# Placa_Motor_Esquematico.net
KiCad netlist of a schematic drawn in Altium Designer
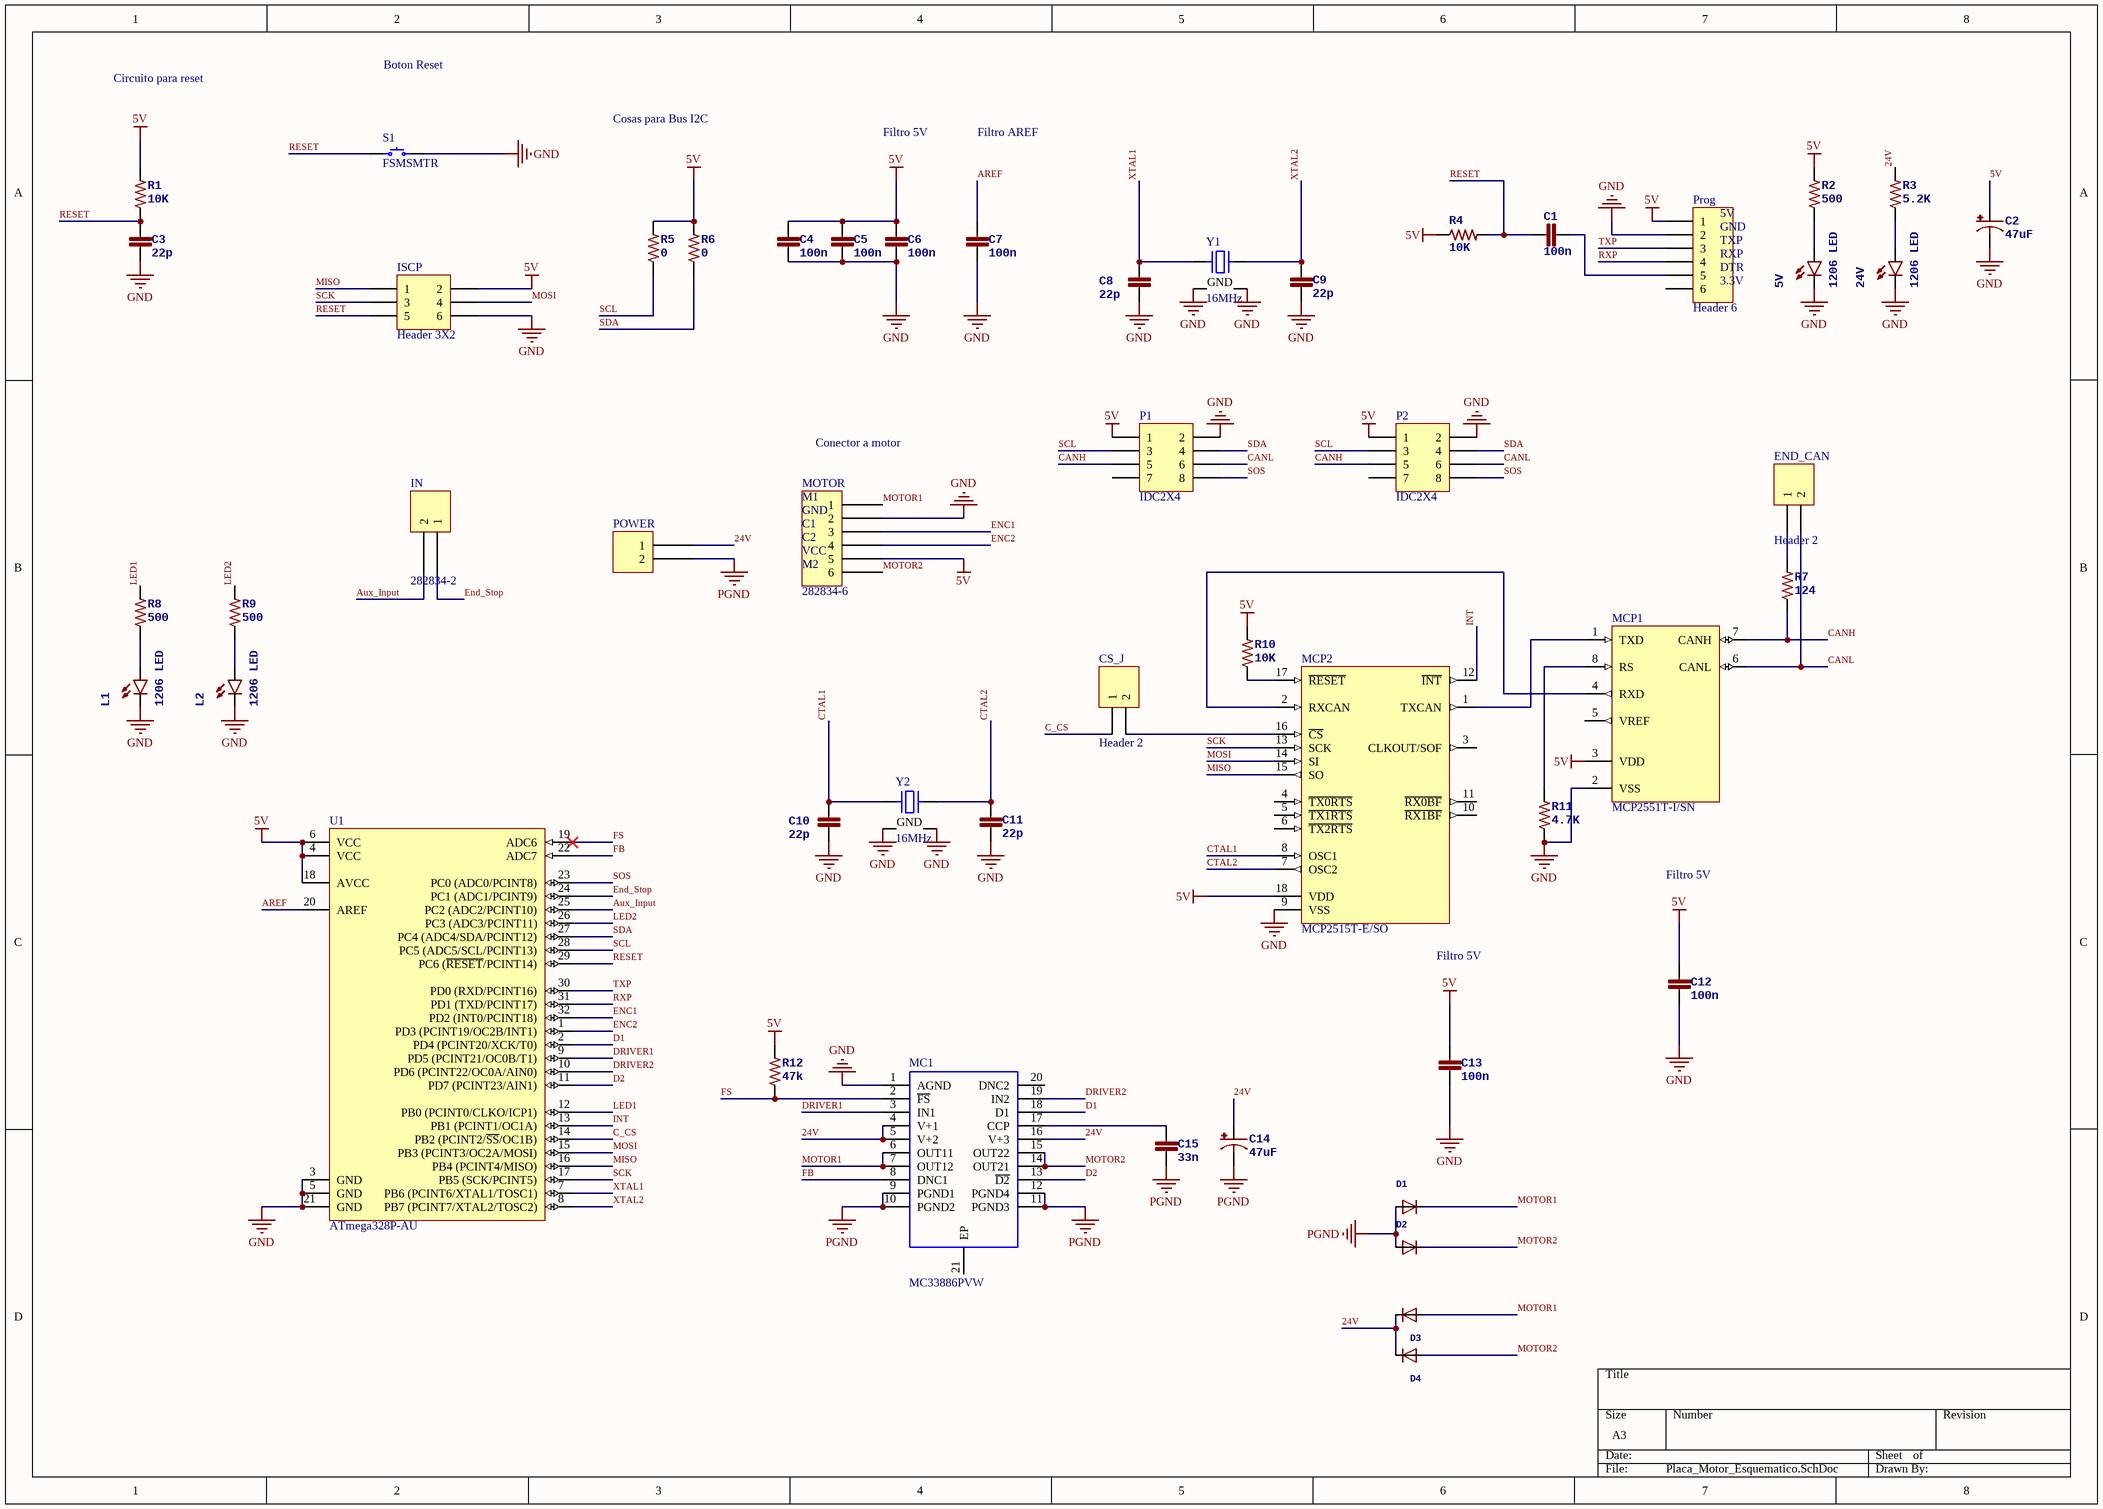
[diagram p0: Placa_Motor_Esquematico.SchDoc]

(export (version "E")
  (design (tool "Eeschema 10.0.6"))
  (components
    (comp (ref "5V")
      (value "1206 LED")
      (footprint "LED-1206")
      (libsource (lib "SparkFun-LED") (part "LED1206"))
    )
    (comp (ref "24V")
      (value "1206 LED")
      (footprint "LED-1206")
      (libsource (lib "SparkFun-LED") (part "LED1206"))
    )
    (comp (ref "C1") (value "100n") (footprint "0805") (libsource (lib "") (part "CAP0805_1")))
    (comp (ref "C2")
      (value "47uF")
      (footprint "PANASONIC_D")
      (libsource (lib "SparkFun-Capacitors") (part "47UF-50V-20%(ELECT)"))
    )
    (comp (ref "C3") (value "22p") (footprint "0805") (libsource (lib "SparkFun-Passives") (part "CAP0805")))
    (comp (ref "C4") (value "100n") (footprint "0805") (libsource (lib "SparkFun-Passives") (part "CAP0805")))
    (comp (ref "C5") (value "100n") (footprint "0805") (libsource (lib "SparkFun-Passives") (part "CAP0805")))
    (comp (ref "C6") (value "100n") (footprint "0805") (libsource (lib "SparkFun-Passives") (part "CAP0805")))
    (comp (ref "C7") (value "100n") (footprint "0805") (libsource (lib "SparkFun-Passives") (part "CAP0805")))
    (comp (ref "C8") (value "22p") (footprint "0805") (libsource (lib "SparkFun-Passives") (part "CAP0805")))
    (comp (ref "C9") (value "22p") (footprint "0805") (libsource (lib "SparkFun-Passives") (part "CAP0805")))
    (comp (ref "C10") (value "22p") (footprint "0805") (libsource (lib "SparkFun-Passives") (part "CAP0805")))
    (comp (ref "C11") (value "22p") (footprint "0805") (libsource (lib "SparkFun-Passives") (part "CAP0805")))
    (comp (ref "C12")
      (value "100n")
      (footprint "0805")
      (libsource (lib "SparkFun-Passives") (part "CAP0805"))
    )
    (comp (ref "C13")
      (value "100n")
      (footprint "0805")
      (libsource (lib "SparkFun-Passives") (part "CAP0805"))
    )
    (comp (ref "C14")
      (value "47uF")
      (footprint "PANASONIC_D")
      (libsource (lib "SparkFun-Capacitors") (part "47UF-50V-20%(ELECT)"))
    )
    (comp (ref "C15") (value "33n") (footprint "0805") (libsource (lib "SparkFun-Passives") (part "CAP0805")))
    (comp (ref "CS_J")
      (value "Header 2")
      (footprint "HDR1X2")
      (description "Header, 2-Pin")
      (fields (field (name "PUBLISHER") "Altium Limited"))
      (libsource (lib "Miscellaneous Connectors") (part "Header 2"))
    )
    (comp (ref "D1")
      (value "SBR3U40P1-7")
      (footprint "POWERDI-123")
      (libsource (lib "diodes-inc") (part "DFLS1100-7"))
    )
    (comp (ref "D2")
      (value "SBR3U40P1-7")
      (footprint "POWERDI-123")
      (libsource (lib "diodes-inc") (part "DFLS1100-7"))
    )
    (comp (ref "D3")
      (value "SBR3U40P1-7")
      (footprint "POWERDI-123")
      (libsource (lib "diodes-inc") (part "DFLS1100-7"))
    )
    (comp (ref "D4")
      (value "SBR3U40P1-7")
      (footprint "POWERDI-123")
      (libsource (lib "diodes-inc") (part "DFLS1100-7"))
    )
    (comp (ref "END_CAN")
      (value "Header 2")
      (footprint "HDR1X2")
      (description "Header, 2-Pin")
      (fields (field (name "PUBLISHER") "Altium Limited"))
      (libsource (lib "Miscellaneous Connectors") (part "Header 2"))
    )
    (comp (ref "IN")
      (value "282834-2")
      (footprint "TE 282834-2")
      (description "TERM BLOCK 2POS SIDE ENT 2.54MM")
      (fields (field (name "MANUFACTURER") "TE Connectivity AMP Connectors") (field (name "VOLTAGE") "150V"))
      (libsource (lib "Connector - Terminal Block") (part "2 Pin"))
    )
    (comp (ref "ISCP")
      (value "Header 3X2")
      (footprint "HDR2X3")
      (description "Header, 3-Pin, Dual row")
      (fields (field (name "PUBLISHER") "Altium Limited"))
      (libsource (lib "Miscellaneous Connectors") (part "Header 3X2"))
    )
    (comp (ref "L1")
      (value "1206 LED")
      (footprint "LED-1206")
      (libsource (lib "SparkFun-LED") (part "LED1206"))
    )
    (comp (ref "L2")
      (value "1206 LED")
      (footprint "LED-1206")
      (libsource (lib "SparkFun-LED") (part "LED1206"))
    )
    (comp (ref "MC1")
      (value "MC33886PVW")
      (footprint "SOIC127P1420X340-21N")
      (description "Motor / Motion / Ignition Controllers & Drivers 5.0 A H-BRIDGE")
      (libsource (lib "MC33886PVW") (part "MC33886PVW"))
    )
    (comp (ref "MCP1")
      (value "MCP2551T-I/SN")
      (footprint "SOIC-SN8_N")
      (description "High-Speed CAN Transceiver, 8-Pin SOIC, Industrial Temperature, Tape and Reel")
      (fields (field (name "PUBLISHER") "Altium Limited"))
      (libsource (lib "Microchip Interface") (part "MCP2551T-I/SN"))
    )
    (comp (ref "MCP2")
      (value "MCP2515T-E/SO")
      (footprint "SOIC-SO18_N")
      (description "Stand-Alone CAN Controller With SPI Interface, 18-Pin SOIC, Extended Temperature, Tape and Reel")
      (fields (field (name "PUBLISHER") "Altium Limited"))
      (libsource (lib "Microchip Interface") (part "MCP2515T-E/SO"))
    )
    (comp (ref "MOTOR")
      (value "282834-6")
      (footprint "TE 282834-6")
      (description "TERM BLOCK 6POS SIDE ENT 2.54MM")
      (fields (field (name "MANUFACTURER") "TE Connectivity AMP Connectors") (field (name "VOLTAGE") "150V"))
      (libsource (lib "Connector - Terminal Block") (part "6 Pin"))
    )
    (comp (ref "P1")
      (value "IDC2X4")
      (footprint "IDC:IDC2X4")
      (description "Header, 4-Pin, Dual row")
      (fields (field (name "PUBLISHER") "Altium Limited"))
      (libsource (lib "IDC") (part "IDC2X4"))
    )
    (comp (ref "P2")
      (value "IDC2X4")
      (footprint "IDC:IDC2X4")
      (description "Header, 4-Pin, Dual row")
      (fields (field (name "PUBLISHER") "Altium Limited"))
      (libsource (lib "IDC") (part "IDC2X4"))
    )
    (comp (ref "POWER")
      (value "20020110-D021A01LF")
      (footprint "FCI 06-381-2PIN")
      (description "TERM BLOCK HDR 2POS R/A 3.81MM")
      (fields (field (name "MANUFACTURER") "FCI") (field (name "VOLTAGE") "300V"))
      (libsource (lib "") (part "2 Pin_1"))
    )
    (comp (ref "Prog")
      (value "Header 6")
      (footprint "HDR1X6")
      (description "Header, 6-Pin")
      (fields (field (name "PUBLISHER") "Altium Limited"))
      (libsource (lib "Miscellaneous Connectors") (part "Header 6"))
    )
    (comp (ref "R1")
      (value "10K")
      (footprint "0805")
      (libsource (lib "SparkFun-Passives") (part "RESISTOR0805-RES"))
    )
    (comp (ref "R2")
      (value "500")
      (footprint "0805")
      (libsource (lib "SparkFun-Passives") (part "RESISTOR0805-RES"))
    )
    (comp (ref "R3")
      (value "5.2K")
      (footprint "0805")
      (libsource (lib "SparkFun-Passives") (part "RESISTOR0805-RES"))
    )
    (comp (ref "R4")
      (value "10K")
      (footprint "0805")
      (libsource (lib "SparkFun-Passives") (part "RESISTOR0805-RES"))
    )
    (comp (ref "R5")
      (value "0")
      (footprint "0805")
      (libsource (lib "SparkFun-Passives") (part "RESISTOR0805-RES"))
    )
    (comp (ref "R6")
      (value "0")
      (footprint "0805")
      (libsource (lib "SparkFun-Passives") (part "RESISTOR0805-RES"))
    )
    (comp (ref "R7")
      (value "124")
      (footprint "0805")
      (libsource (lib "SparkFun-Passives") (part "RESISTOR0805-RES"))
    )
    (comp (ref "R8")
      (value "500")
      (footprint "0805")
      (libsource (lib "SparkFun-Passives") (part "RESISTOR0805-RES"))
    )
    (comp (ref "R9")
      (value "500")
      (footprint "0805")
      (libsource (lib "SparkFun-Passives") (part "RESISTOR0805-RES"))
    )
    (comp (ref "R10")
      (value "10K")
      (footprint "0805")
      (libsource (lib "SparkFun-Passives") (part "RESISTOR0805-RES"))
    )
    (comp (ref "R11")
      (value "4.7K")
      (footprint "0805")
      (libsource (lib "SparkFun-Passives") (part "RESISTOR0805-RES"))
    )
    (comp (ref "R12")
      (value "47k")
      (footprint "0805")
      (libsource (lib "SparkFun-Passives") (part "RESISTOR0805-RES"))
    )
    (comp (ref "S1")
      (value "FSMSMTR")
      (footprint "TE FSMSMTR")
      (description "SWITCH TACTILE SPST-NO 0.05A 24V")
      (fields (field (name "MANUFACTURER") "TE Connectivity Alcoswitch Switches"))
      (libsource (lib "Button - Tactile") (part "SPST-NO 2 PIN"))
    )
    (comp (ref "U1")
      (value "ATmega328P-AU")
      (footprint "32A_N")
      (fields (field (name "PUBLISHER") "Altium Limited"))
      (libsource (lib "Atmel Microcontroller 8-Bit megaAVR") (part "ATmega328P-AU"))
    )
    (comp (ref "Y1")
      (value "16MHz")
      (footprint "NDK NX3225SA")
      (description "CRYSTAL 16.0000MHZ 8PF SMD")
      (fields (field (name "PART NUMBER") "NX3225SA-16.000MHZ-STD-CSR-1") (field (name "MANUFACTURER") "NDK"))
      (libsource (lib "Oscillator - Crystal") (part "NDK Crystal NX3225SA"))
    )
    (comp (ref "Y2")
      (value "16MHz")
      (footprint "NDK NX3225SA")
      (description "CRYSTAL 16.0000MHZ 8PF SMD")
      (fields (field (name "PART NUMBER") "NX3225SA-16.000MHZ-STD-CSR-1") (field (name "MANUFACTURER") "NDK"))
      (libsource (lib "Oscillator - Crystal") (part "NDK Crystal NX3225SA"))
    )
  )
  (nets
    (net (code "1") (name "/24V") (class "Default")
      (node (ref "C14") (pin "+") (pinfunction "+_+") (pintype "passive"))
      (node (ref "D3") (pin "C") (pinfunction "C_C") (pintype "passive"))
      (node (ref "D4") (pin "C") (pinfunction "C_C") (pintype "passive"))
      (node (ref "MC1") (pin "16") (pinfunction "V+3_16") (pintype "passive"))
      (node (ref "MC1") (pin "4") (pinfunction "V+1_4") (pintype "passive"))
      (node (ref "MC1") (pin "5") (pinfunction "V+2_5") (pintype "passive"))
      (node (ref "POWER") (pin "1") (pinfunction "1_1") (pintype "passive"))
      (node (ref "R3") (pin "2") (pinfunction "2_2") (pintype "passive"))
    )
    (net (code "2") (name "/AREF") (class "Default")
      (node (ref "C7") (pin "1") (pinfunction "1_1") (pintype "passive"))
      (node (ref "U1") (pin "20") (pinfunction "AREF_20") (pintype "passive"))
    )
    (net (code "3") (name "/Aux_Input") (class "Default")
      (node (ref "IN") (pin "2") (pinfunction "2_2") (pintype "passive"))
      (node (ref "U1") (pin "25") (pinfunction "PC2_(ADC2/PCINT10)_25") (pintype "bidirectional"))
    )
    (net (code "4") (name "/CANH") (class "Default")
      (node (ref "MCP1") (pin "7") (pinfunction "CANH_7") (pintype "bidirectional"))
      (node (ref "P1") (pin "5") (pinfunction "5_5") (pintype "passive"))
      (node (ref "P2") (pin "5") (pinfunction "5_5") (pintype "passive"))
      (node (ref "R7") (pin "1") (pinfunction "1_1") (pintype "passive"))
    )
    (net (code "5") (name "/CANL") (class "Default")
      (node (ref "END_CAN") (pin "2") (pinfunction "2_2") (pintype "passive"))
      (node (ref "MCP1") (pin "6") (pinfunction "CANL_6") (pintype "bidirectional"))
      (node (ref "P1") (pin "6") (pinfunction "6_6") (pintype "passive"))
      (node (ref "P2") (pin "6") (pinfunction "6_6") (pintype "passive"))
    )
    (net (code "6") (name "/CTAL1") (class "Default")
      (node (ref "C10") (pin "1") (pinfunction "1_1") (pintype "passive"))
      (node (ref "MCP2") (pin "8") (pinfunction "OSC1_8") (pintype "input"))
      (node (ref "Y2") (pin "1") (pinfunction "1_1") (pintype "passive"))
    )
    (net (code "7") (name "/CTAL2") (class "Default")
      (node (ref "C11") (pin "1") (pinfunction "1_1") (pintype "passive"))
      (node (ref "MCP2") (pin "7") (pinfunction "OSC2_7") (pintype "output"))
      (node (ref "Y2") (pin "3") (pinfunction "3_3") (pintype "passive"))
    )
    (net (code "8") (name "/C_CS") (class "Default")
      (node (ref "CS_J") (pin "1") (pinfunction "1_1") (pintype "passive"))
      (node (ref "U1") (pin "14") (pinfunction "PB2_(PCINT2/~{SS}/OC1B)_14") (pintype "bidirectional"))
    )
    (net (code "9") (name "/D1") (class "Default")
      (node (ref "MC1") (pin "18") (pinfunction "D1_18") (pintype "passive"))
      (node (ref "U1") (pin "2") (pinfunction "PD4_(PCINT20/XCK/T0)_2") (pintype "bidirectional"))
    )
    (net (code "10") (name "/D2") (class "Default")
      (node (ref "MC1") (pin "13") (pinfunction "D2_13") (pintype "passive"))
      (node (ref "U1") (pin "11") (pinfunction "PD7_(PCINT23/AIN1)_11") (pintype "bidirectional"))
    )
    (net (code "11") (name "/DRIVER1") (class "Default")
      (node (ref "MC1") (pin "3") (pinfunction "IN1_3") (pintype "passive"))
      (node (ref "U1") (pin "9") (pinfunction "PD5_(PCINT21/OC0B/T1)_9") (pintype "bidirectional"))
    )
    (net (code "12") (name "/DRIVER2") (class "Default")
      (node (ref "MC1") (pin "19") (pinfunction "IN2_19") (pintype "passive"))
      (node (ref "U1") (pin "10") (pinfunction "PD6_(PCINT22/OC0A/AIN0)_10") (pintype "bidirectional"))
    )
    (net (code "13") (name "/ENC1") (class "Default")
      (node (ref "MOTOR") (pin "3") (pinfunction "3_3") (pintype "passive"))
      (node (ref "U1") (pin "32") (pinfunction "PD2_(INT0/PCINT18)_32") (pintype "bidirectional"))
    )
    (net (code "14") (name "/ENC2") (class "Default")
      (node (ref "MOTOR") (pin "4") (pinfunction "4_4") (pintype "passive"))
      (node (ref "U1") (pin "1") (pinfunction "PD3_(PCINT19/OC2B/INT1)_1") (pintype "bidirectional"))
    )
    (net (code "15") (name "/End_Stop") (class "Default")
      (node (ref "IN") (pin "1") (pinfunction "1_1") (pintype "passive"))
      (node (ref "U1") (pin "24") (pinfunction "PC1_(ADC1/PCINT9)_24") (pintype "bidirectional"))
    )
    (net (code "16") (name "/FB") (class "Default")
      (node (ref "MC1") (pin "8") (pinfunction "DNC1_8") (pintype "passive"))
      (node (ref "U1") (pin "22") (pinfunction "ADC7_22") (pintype "input"))
    )
    (net (code "17") (name "/FS") (class "Default")
      (node (ref "MC1") (pin "2") (pinfunction "FS_2") (pintype "passive"))
      (node (ref "R12") (pin "1") (pinfunction "1_1") (pintype "passive"))
      (node (ref "U1") (pin "19") (pinfunction "ADC6_19") (pintype "input"))
    )
    (net (code "18") (name "/INT") (class "Default")
      (node (ref "MCP2") (pin "12") (pinfunction "~{INT}_12") (pintype "output"))
      (node (ref "U1") (pin "13") (pinfunction "PB1_(PCINT1/OC1A)_13") (pintype "bidirectional"))
    )
    (net (code "19") (name "/LED1") (class "Default")
      (node (ref "R8") (pin "2") (pinfunction "2_2") (pintype "passive"))
      (node (ref "U1") (pin "12") (pinfunction "PB0_(PCINT0/CLKO/ICP1)_12") (pintype "bidirectional"))
    )
    (net (code "20") (name "/LED2") (class "Default")
      (node (ref "R9") (pin "2") (pinfunction "2_2") (pintype "passive"))
      (node (ref "U1") (pin "26") (pinfunction "PC3_(ADC3/PCINT11)_26") (pintype "bidirectional"))
    )
    (net (code "21") (name "/MISO") (class "Default")
      (node (ref "ISCP") (pin "1") (pinfunction "1_1") (pintype "passive"))
      (node (ref "MCP2") (pin "15") (pinfunction "SO_15") (pintype "output"))
      (node (ref "U1") (pin "16") (pinfunction "PB4_(PCINT4/MISO)_16") (pintype "bidirectional"))
    )
    (net (code "22") (name "/MOSI") (class "Default")
      (node (ref "ISCP") (pin "4") (pinfunction "4_4") (pintype "passive"))
      (node (ref "MCP2") (pin "14") (pinfunction "SI_14") (pintype "input"))
      (node (ref "U1") (pin "15") (pinfunction "PB3_(PCINT3/OC2A/MOSI)_15") (pintype "bidirectional"))
    )
    (net (code "23") (name "/MOTOR1") (class "Default")
      (node (ref "D1") (pin "C") (pinfunction "C_C") (pintype "passive"))
      (node (ref "D3") (pin "A") (pinfunction "A_A") (pintype "passive"))
      (node (ref "MC1") (pin "6") (pinfunction "OUT11_6") (pintype "passive"))
      (node (ref "MC1") (pin "7") (pinfunction "OUT12_7") (pintype "passive"))
      (node (ref "MOTOR") (pin "1") (pinfunction "1_1") (pintype "passive"))
    )
    (net (code "24") (name "/MOTOR2") (class "Default")
      (node (ref "D2") (pin "C") (pinfunction "C_C") (pintype "passive"))
      (node (ref "D4") (pin "A") (pinfunction "A_A") (pintype "passive"))
      (node (ref "MC1") (pin "14") (pinfunction "OUT21_14") (pintype "passive"))
      (node (ref "MC1") (pin "15") (pinfunction "OUT22_15") (pintype "passive"))
      (node (ref "MOTOR") (pin "6") (pinfunction "6_6") (pintype "passive"))
    )
    (net (code "25") (name "/RESET") (class "Default")
      (node (ref "C1") (pin "1") (pinfunction "1_1") (pintype "passive"))
      (node (ref "C3") (pin "1") (pinfunction "1_1") (pintype "passive"))
      (node (ref "ISCP") (pin "5") (pinfunction "5_5") (pintype "passive"))
      (node (ref "R1") (pin "1") (pinfunction "1_1") (pintype "passive"))
      (node (ref "R4") (pin "2") (pinfunction "2_2") (pintype "passive"))
      (node (ref "S1") (pin "1") (pinfunction "1_1") (pintype "passive"))
      (node (ref "U1") (pin "29") (pinfunction "PC6_(~{RESET}/PCINT14)_29") (pintype "bidirectional"))
    )
    (net (code "26") (name "/RXP") (class "Default")
      (node (ref "Prog") (pin "4") (pinfunction "4_4") (pintype "passive"))
      (node (ref "U1") (pin "31") (pinfunction "PD1_(TXD/PCINT17)_31") (pintype "bidirectional"))
    )
    (net (code "27") (name "/SCK") (class "Default")
      (node (ref "ISCP") (pin "3") (pinfunction "3_3") (pintype "passive"))
      (node (ref "MCP2") (pin "13") (pinfunction "SCK_13") (pintype "input"))
      (node (ref "U1") (pin "17") (pinfunction "PB5_(SCK/PCINT5)_17") (pintype "bidirectional"))
    )
    (net (code "28") (name "/SCL") (class "Default")
      (node (ref "P1") (pin "3") (pinfunction "3_3") (pintype "passive"))
      (node (ref "P2") (pin "3") (pinfunction "3_3") (pintype "passive"))
      (node (ref "R5") (pin "1") (pinfunction "1_1") (pintype "passive"))
      (node (ref "U1") (pin "28") (pinfunction "PC5_(ADC5/SCL/PCINT13)_28") (pintype "bidirectional"))
    )
    (net (code "29") (name "/SDA") (class "Default")
      (node (ref "P1") (pin "4") (pinfunction "4_4") (pintype "passive"))
      (node (ref "P2") (pin "4") (pinfunction "4_4") (pintype "passive"))
      (node (ref "R6") (pin "1") (pinfunction "1_1") (pintype "passive"))
      (node (ref "U1") (pin "27") (pinfunction "PC4_(ADC4/SDA/PCINT12)_27") (pintype "bidirectional"))
    )
    (net (code "30") (name "/SOS") (class "Default")
      (node (ref "P1") (pin "8") (pinfunction "8_8") (pintype "passive"))
      (node (ref "P2") (pin "8") (pinfunction "8_8") (pintype "passive"))
      (node (ref "U1") (pin "23") (pinfunction "PC0_(ADC0/PCINT8)_23") (pintype "bidirectional"))
    )
    (net (code "31") (name "/TXP") (class "Default")
      (node (ref "Prog") (pin "3") (pinfunction "3_3") (pintype "passive"))
      (node (ref "U1") (pin "30") (pinfunction "PD0_(RXD/PCINT16)_30") (pintype "bidirectional"))
    )
    (net (code "32") (name "/XTAL1") (class "Default")
      (node (ref "C8") (pin "1") (pinfunction "1_1") (pintype "passive"))
      (node (ref "U1") (pin "7") (pinfunction "PB6_(PCINT6/XTAL1/TOSC1)_7") (pintype "bidirectional"))
      (node (ref "Y1") (pin "1") (pinfunction "1_1") (pintype "passive"))
    )
    (net (code "33") (name "/XTAL2") (class "Default")
      (node (ref "C9") (pin "1") (pinfunction "1_1") (pintype "passive"))
      (node (ref "U1") (pin "8") (pinfunction "PB7_(PCINT7/XTAL2/TOSC2)_8") (pintype "bidirectional"))
      (node (ref "Y1") (pin "3") (pinfunction "3_3") (pintype "passive"))
    )
    (net (code "34") (name "5V") (class "Default")
      (node (ref "C12") (pin "1") (pinfunction "1_1") (pintype "passive"))
      (node (ref "C13") (pin "1") (pinfunction "1_1") (pintype "passive"))
      (node (ref "C2") (pin "+") (pinfunction "+_+") (pintype "passive"))
      (node (ref "C4") (pin "1") (pinfunction "1_1") (pintype "passive"))
      (node (ref "C5") (pin "1") (pinfunction "1_1") (pintype "passive"))
      (node (ref "C6") (pin "1") (pinfunction "1_1") (pintype "passive"))
      (node (ref "ISCP") (pin "2") (pinfunction "2_2") (pintype "passive"))
      (node (ref "MCP1") (pin "3") (pinfunction "VDD_3") (pintype "power_in"))
      (node (ref "MCP2") (pin "18") (pinfunction "VDD_18") (pintype "power_in"))
      (node (ref "MOTOR") (pin "5") (pinfunction "5_5") (pintype "passive"))
      (node (ref "P1") (pin "1") (pinfunction "1_1") (pintype "passive"))
      (node (ref "P2") (pin "1") (pinfunction "1_1") (pintype "passive"))
      (node (ref "Prog") (pin "1") (pinfunction "1_1") (pintype "passive"))
      (node (ref "R1") (pin "2") (pinfunction "2_2") (pintype "passive"))
      (node (ref "R10") (pin "2") (pinfunction "2_2") (pintype "passive"))
      (node (ref "R12") (pin "2") (pinfunction "2_2") (pintype "passive"))
      (node (ref "R2") (pin "2") (pinfunction "2_2") (pintype "passive"))
      (node (ref "R4") (pin "1") (pinfunction "1_1") (pintype "passive"))
      (node (ref "R5") (pin "2") (pinfunction "2_2") (pintype "passive"))
      (node (ref "R6") (pin "2") (pinfunction "2_2") (pintype "passive"))
      (node (ref "U1") (pin "18") (pinfunction "AVCC_18") (pintype "power_in"))
      (node (ref "U1") (pin "4") (pinfunction "VCC_4") (pintype "power_in"))
      (node (ref "U1") (pin "6") (pinfunction "VCC_6") (pintype "power_in"))
    )
    (net (code "35") (name "GND") (class "Default")
      (node (ref "24V") (pin "C") (pinfunction "C_C") (pintype "passive"))
      (node (ref "5V") (pin "C") (pinfunction "C_C") (pintype "passive"))
      (node (ref "C10") (pin "2") (pinfunction "2_2") (pintype "passive"))
      (node (ref "C11") (pin "2") (pinfunction "2_2") (pintype "passive"))
      (node (ref "C12") (pin "2") (pinfunction "2_2") (pintype "passive"))
      (node (ref "C13") (pin "2") (pinfunction "2_2") (pintype "passive"))
      (node (ref "C2") (pin "-") (pinfunction "-_-") (pintype "passive"))
      (node (ref "C3") (pin "2") (pinfunction "2_2") (pintype "passive"))
      (node (ref "C4") (pin "2") (pinfunction "2_2") (pintype "passive"))
      (node (ref "C5") (pin "2") (pinfunction "2_2") (pintype "passive"))
      (node (ref "C6") (pin "2") (pinfunction "2_2") (pintype "passive"))
      (node (ref "C7") (pin "2") (pinfunction "2_2") (pintype "passive"))
      (node (ref "C8") (pin "2") (pinfunction "2_2") (pintype "passive"))
      (node (ref "C9") (pin "2") (pinfunction "2_2") (pintype "passive"))
      (node (ref "ISCP") (pin "6") (pinfunction "6_6") (pintype "passive"))
      (node (ref "L1") (pin "C") (pinfunction "C_C") (pintype "passive"))
      (node (ref "L2") (pin "C") (pinfunction "C_C") (pintype "passive"))
      (node (ref "MC1") (pin "1") (pinfunction "AGND_1") (pintype "passive"))
      (node (ref "MCP1") (pin "2") (pinfunction "VSS_2") (pintype "power_in"))
      (node (ref "MCP2") (pin "9") (pinfunction "VSS_9") (pintype "power_in"))
      (node (ref "MOTOR") (pin "2") (pinfunction "2_2") (pintype "passive"))
      (node (ref "P1") (pin "2") (pinfunction "2_2") (pintype "passive"))
      (node (ref "P2") (pin "2") (pinfunction "2_2") (pintype "passive"))
      (node (ref "Prog") (pin "2") (pinfunction "2_2") (pintype "passive"))
      (node (ref "R11") (pin "1") (pinfunction "1_1") (pintype "passive"))
      (node (ref "S1") (pin "2") (pinfunction "2_2") (pintype "passive"))
      (node (ref "U1") (pin "21") (pinfunction "GND_21") (pintype "power_in"))
      (node (ref "U1") (pin "3") (pinfunction "GND_3") (pintype "power_in"))
      (node (ref "U1") (pin "5") (pinfunction "GND_5") (pintype "power_in"))
      (node (ref "Y1") (pin "2") (pinfunction "GND_2") (pintype "passive"))
      (node (ref "Y1") (pin "4") (pinfunction "GND_4") (pintype "passive"))
      (node (ref "Y2") (pin "2") (pinfunction "GND_2") (pintype "passive"))
      (node (ref "Y2") (pin "4") (pinfunction "GND_4") (pintype "passive"))
    )
    (net (code "36") (name "Net-(5V-PadA)") (class "Default")
      (node (ref "5V") (pin "A") (pinfunction "A_A") (pintype "passive"))
      (node (ref "R2") (pin "1") (pinfunction "1_1") (pintype "passive"))
    )
    (net (code "37") (name "Net-(24V-PadA)") (class "Default")
      (node (ref "24V") (pin "A") (pinfunction "A_A") (pintype "passive"))
      (node (ref "R3") (pin "1") (pinfunction "1_1") (pintype "passive"))
    )
    (net (code "38") (name "Net-(C1-Pad2)") (class "Default")
      (node (ref "C1") (pin "2") (pinfunction "2_2") (pintype "passive"))
      (node (ref "Prog") (pin "5") (pinfunction "5_5") (pintype "passive"))
    )
    (net (code "39") (name "Net-(END_CAN-Pad1)") (class "Default")
      (node (ref "END_CAN") (pin "1") (pinfunction "1_1") (pintype "passive"))
      (node (ref "R7") (pin "2") (pinfunction "2_2") (pintype "passive"))
    )
    (net (code "40") (name "Net-(L1-PadA)") (class "Default")
      (node (ref "L1") (pin "A") (pinfunction "A_A") (pintype "passive"))
      (node (ref "R8") (pin "1") (pinfunction "1_1") (pintype "passive"))
    )
    (net (code "41") (name "Net-(L2-PadA)") (class "Default")
      (node (ref "L2") (pin "A") (pinfunction "A_A") (pintype "passive"))
      (node (ref "R9") (pin "1") (pinfunction "1_1") (pintype "passive"))
    )
    (net (code "42") (name "Net-(MC1-CCP)") (class "Default")
      (node (ref "C15") (pin "1") (pinfunction "1_1") (pintype "passive"))
      (node (ref "MC1") (pin "17") (pinfunction "CCP_17") (pintype "passive"))
    )
    (net (code "43") (name "Net-(MCP1-RS)") (class "Default")
      (node (ref "MCP1") (pin "8") (pinfunction "RS_8") (pintype "input"))
      (node (ref "R11") (pin "2") (pinfunction "2_2") (pintype "passive"))
    )
    (net (code "44") (name "Net-(MCP1-RXD)") (class "Default")
      (node (ref "MCP1") (pin "4") (pinfunction "RXD_4") (pintype "output"))
      (node (ref "MCP2") (pin "2") (pinfunction "RXCAN_2") (pintype "input"))
    )
    (net (code "45") (name "Net-(MCP1-TXD)") (class "Default")
      (node (ref "MCP1") (pin "1") (pinfunction "TXD_1") (pintype "input"))
      (node (ref "MCP2") (pin "1") (pinfunction "TXCAN_1") (pintype "output"))
    )
    (net (code "46") (name "Net-(MCP2-~{CS})") (class "Default")
      (node (ref "CS_J") (pin "2") (pinfunction "2_2") (pintype "passive"))
      (node (ref "MCP2") (pin "16") (pinfunction "~{CS}_16") (pintype "input"))
    )
    (net (code "47") (name "Net-(MCP2-~{RESET})") (class "Default")
      (node (ref "MCP2") (pin "17") (pinfunction "~{RESET}_17") (pintype "input"))
      (node (ref "R10") (pin "1") (pinfunction "1_1") (pintype "passive"))
    )
    (net (code "48") (name "PGND") (class "Default")
      (node (ref "C14") (pin "-") (pinfunction "-_-") (pintype "passive"))
      (node (ref "C15") (pin "2") (pinfunction "2_2") (pintype "passive"))
      (node (ref "D1") (pin "A") (pinfunction "A_A") (pintype "passive"))
      (node (ref "D2") (pin "A") (pinfunction "A_A") (pintype "passive"))
      (node (ref "MC1") (pin "10") (pinfunction "PGND2_10") (pintype "passive"))
      (node (ref "MC1") (pin "11") (pinfunction "PGND3_11") (pintype "passive"))
      (node (ref "MC1") (pin "12") (pinfunction "PGND4_12") (pintype "passive"))
      (node (ref "MC1") (pin "9") (pinfunction "PGND1_9") (pintype "passive"))
      (node (ref "POWER") (pin "2") (pinfunction "2_2") (pintype "passive"))
    )
    (net (code "49") (name "unconnected-(MC1-DNC2-Pad20)") (class "Default")
      (node (ref "MC1") (pin "20") (pinfunction "DNC2_20") (pintype "passive"))
    )
    (net (code "50") (name "unconnected-(MC1-EP-Pad21)") (class "Default")
      (node (ref "MC1") (pin "21") (pinfunction "EP_21") (pintype "passive"))
    )
    (net (code "51") (name "unconnected-(MCP1-VREF-Pad5)") (class "Default")
      (node (ref "MCP1") (pin "5") (pinfunction "VREF_5") (pintype "output"))
    )
    (net (code "52") (name "unconnected-(MCP2-CLKOUT{slash}SOF-Pad3)") (class "Default")
      (node (ref "MCP2") (pin "3") (pinfunction "CLKOUT/SOF_3") (pintype "output"))
    )
    (net (code "53") (name "unconnected-(MCP2-~{RX0BF}-Pad11)") (class "Default")
      (node (ref "MCP2") (pin "11") (pinfunction "~{RX0BF}_11") (pintype "output"))
    )
    (net (code "54") (name "unconnected-(MCP2-~{RX1BF}-Pad10)") (class "Default")
      (node (ref "MCP2") (pin "10") (pinfunction "~{RX1BF}_10") (pintype "output"))
    )
    (net (code "55") (name "unconnected-(MCP2-~{TX0RTS}-Pad4)") (class "Default")
      (node (ref "MCP2") (pin "4") (pinfunction "~{TX0RTS}_4") (pintype "input"))
    )
    (net (code "56") (name "unconnected-(MCP2-~{TX1RTS}-Pad5)") (class "Default")
      (node (ref "MCP2") (pin "5") (pinfunction "~{TX1RTS}_5") (pintype "input"))
    )
    (net (code "57") (name "unconnected-(MCP2-~{TX2RTS}-Pad6)") (class "Default")
      (node (ref "MCP2") (pin "6") (pinfunction "~{TX2RTS}_6") (pintype "input"))
    )
    (net (code "58") (name "unconnected-(P1-Pad7)") (class "Default")
      (node (ref "P1") (pin "7") (pinfunction "7_7") (pintype "passive"))
    )
    (net (code "59") (name "unconnected-(P2-Pad7)") (class "Default")
      (node (ref "P2") (pin "7") (pinfunction "7_7") (pintype "passive"))
    )
    (net (code "60") (name "unconnected-(Prog-Pad6)") (class "Default")
      (node (ref "Prog") (pin "6") (pinfunction "6_6") (pintype "passive"))
    )
  )
)
